# MIXER.net
KiCad netlist of a schematic drawn in Altium Designer
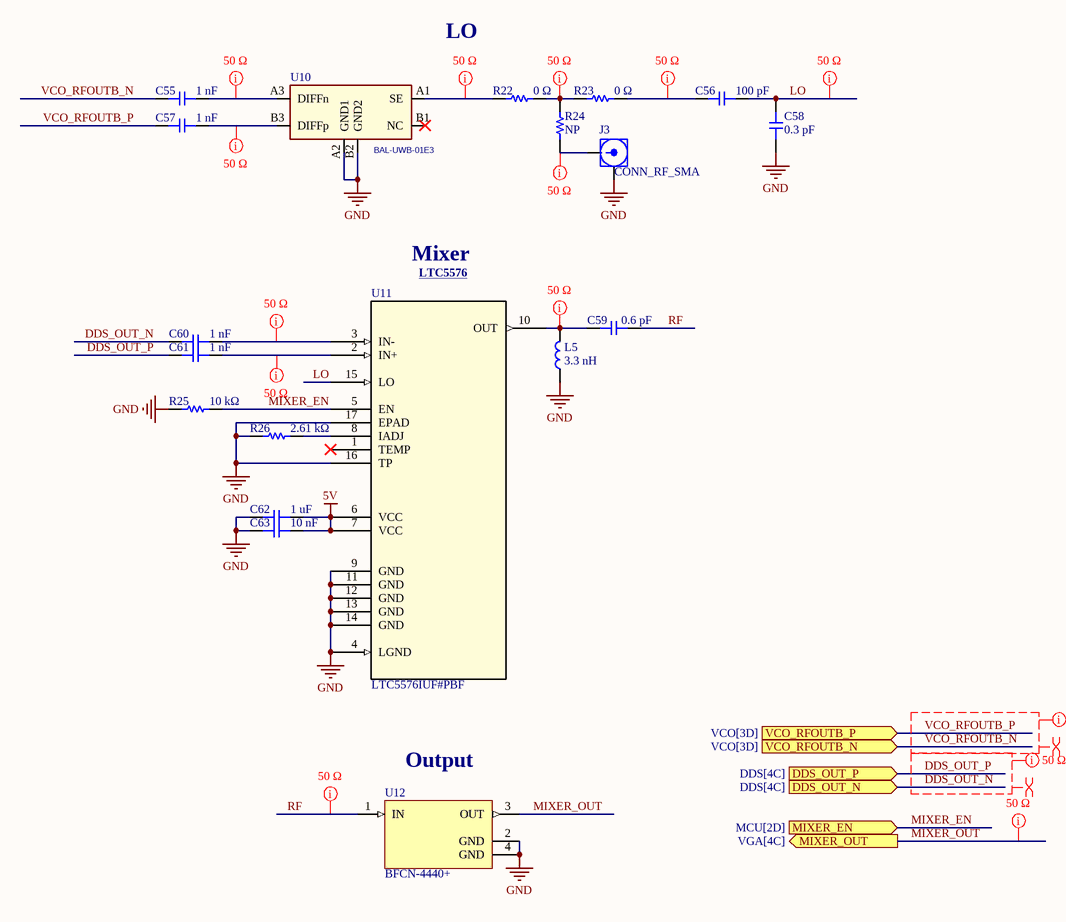
[diagram p0: MIXER.SchDoc]

(export (version "E")
  (design (tool "Eeschema 10.0.6"))
  (components
    (comp (ref "C55")
      (value "1 nF")
      (footprint "CAP_0402")
      (description "50V 1nF X7R ±10% 0402 Multilayer Ceramic Capacitors MLCC - SMD/SMT ROHS")
      (fields
        (field (name "MANUFACTURER") "Yageo")
        (field (name "MANUFACTURER PART NUMBER") "CC0402KRX7R9BB102")
      )
      (libsource (lib "Titan") (part "CAP"))
    )
    (comp (ref "C56")
      (value "100 pF")
      (footprint "CAP_0402")
      (description "50V 100pF NP0 ±5% 0402 Multilayer Ceramic Capacitors MLCC - SMD/SMT ROHS")
      (fields
        (field (name "MANUFACTURER") "Yageo")
        (field (name "MANUFACTURER PART NUMBER") "CC0402JRNPO9BN101")
      )
      (libsource (lib "Titan") (part "CAP"))
    )
    (comp (ref "C57")
      (value "1 nF")
      (footprint "CAP_0402")
      (description "50V 1nF X7R ±10% 0402 Multilayer Ceramic Capacitors MLCC - SMD/SMT ROHS")
      (fields
        (field (name "MANUFACTURER") "Yageo")
        (field (name "MANUFACTURER PART NUMBER") "CC0402KRX7R9BB102")
      )
      (libsource (lib "Titan") (part "CAP"))
    )
    (comp (ref "C58")
      (value "0.3 pF")
      (footprint "CAP_0402")
      (description "50V 0.3pF C0G 0402 Multilayer Ceramic Capacitors MLCC - SMD/SMT ROHS")
      (fields
        (field (name "MANUFACTURER") "Murata Electronics")
        (field (name "MANUFACTURER PART NUMBER") "GJM1555C1HR30WB01D")
      )
      (libsource (lib "Titan") (part "CAP"))
    )
    (comp (ref "C59")
      (value "0.6 pF")
      (footprint "CAP_0402")
      (description "50V 0.6pF C0G 0402 Multilayer Ceramic Capacitors MLCC - SMD/SMT ROHS")
      (fields
        (field (name "MANUFACTURER") "Murata Electronics")
        (field (name "MANUFACTURER PART NUMBER") "GJM1555C1HR60WB01D")
      )
      (libsource (lib "Titan") (part "CAP"))
    )
    (comp (ref "C60")
      (value "1 nF")
      (footprint "CAP_0402")
      (description "50V 1nF X7R ±10% 0402 Multilayer Ceramic Capacitors MLCC - SMD/SMT ROHS")
      (fields
        (field (name "MANUFACTURER") "Yageo")
        (field (name "MANUFACTURER PART NUMBER") "CC0402KRX7R9BB102")
      )
      (libsource (lib "Titan") (part "CAP"))
    )
    (comp (ref "C61")
      (value "1 nF")
      (footprint "CAP_0402")
      (description "50V 1nF X7R ±10% 0402 Multilayer Ceramic Capacitors MLCC - SMD/SMT ROHS")
      (fields
        (field (name "MANUFACTURER") "Yageo")
        (field (name "MANUFACTURER PART NUMBER") "CC0402KRX7R9BB102")
      )
      (libsource (lib "Titan") (part "CAP"))
    )
    (comp (ref "C62")
      (value "1 uF")
      (footprint "CAP_0603")
      (description "25V 1uF X7R ±10% 0603 Multilayer Ceramic Capacitors MLCC - SMD/SMT ROHS")
      (fields
        (field (name "MANUFACTURER") "Samsung Electro-Mechanics")
        (field (name "MANUFACTURER PART NUMBER") "CL10B105KA8NNNC")
      )
      (libsource (lib "Titan") (part "CAP"))
    )
    (comp (ref "C63")
      (value "10 nF")
      (footprint "CAP_0402")
      (description "50V 10nF X7R ±10% 0402 Multilayer Ceramic Capacitors MLCC - SMD/SMT ROHS")
      (fields
        (field (name "MANUFACTURER") "Yageo")
        (field (name "MANUFACTURER PART NUMBER") "CC0402KRX7R9BB103")
      )
      (libsource (lib "Titan") (part "CAP"))
    )
    (comp (ref "J3")
      (value "CONN_RF_SMA")
      (footprint "142-0701-801")
      (description "RF / Coaxial Connector, SMA Coaxial, Straight Jack, Solder, 50 ohm, Beryllium Copper")
      (fields
        (field (name "MANUFACTURER") "Cinch Connectivity Solutions Johnson")
        (field (name "MANUFACTURER PART NUMBER") "142-0701-801")
      )
      (libsource (lib "Titan") (part "CONN_RF_SMA"))
    )
    (comp (ref "L5")
      (value "3.3 nH")
      (footprint "IND_0402")
      (description "Ind RF Chip Unshielded Wirewound 3.3nH 0.1nH 100MHz 30Q-Factor Ferrite 2A 0402 Paper T/R")
      (fields
        (field (name "MANUFACTURER") "Murata Electronics")
        (field (name "MANUFACTURER PART NUMBER") "LQW15AN3N3B80D")
      )
      (libsource (lib "Titan") (part "IND"))
    )
    (comp (ref "R22")
      (value "0 Ω")
      (footprint "RES_0402")
      (description "GENERAL PURPOSE CHIP RESISTOR Metal Glaze/thick Film, 0.0625W, 0ohm, Surface Mount, 0402")
      (fields
        (field (name "MANUFACTURER") "Yageo")
        (field (name "MANUFACTURER PART NUMBER") "RC0402FR-070RL")
      )
      (libsource (lib "Titan") (part "RES"))
    )
    (comp (ref "R23")
      (value "0 Ω")
      (footprint "RES_0402")
      (description "GENERAL PURPOSE CHIP RESISTOR Metal Glaze/thick Film, 0.0625W, 0ohm, Surface Mount, 0402")
      (fields
        (field (name "MANUFACTURER") "Yageo")
        (field (name "MANUFACTURER PART NUMBER") "RC0402FR-070RL")
      )
      (libsource (lib "Titan") (part "RES"))
    )
    (comp (ref "R24")
      (value "NP")
      (footprint "RES_0402")
      (description "Resistor SMD Generic")
      (libsource (lib "Titan") (part "RES"))
    )
    (comp (ref "R25")
      (value "10 kΩ")
      (footprint "RES_0402")
      (description "Res Thick Film 0402 10K Ohm 1% 0.063W(1/16W) ±100ppm/C Pad SMD T/R")
      (fields
        (field (name "MANUFACTURER") "Yageo")
        (field (name "MANUFACTURER PART NUMBER") "RC0402FR-0710KL")
      )
      (libsource (lib "Titan") (part "RES"))
    )
    (comp (ref "R26")
      (value "2.61 kΩ")
      (footprint "RES_0402")
      (description "Fixed Resistor, Thin Film, 0.0625W, 2610ohm, 50V, 1% +/-Tol, 50ppm/Cel, Surface Mount, 0402")
      (fields
        (field (name "MANUFACTURER") "Yageo")
        (field (name "MANUFACTURER PART NUMBER") "RT0402FRE072K61L")
      )
      (libsource (lib "Titan") (part "RES"))
    )
    (comp (ref "U10")
      (value "BAL-UWB-01E3")
      (footprint "ST_CSP6_82x65P2x3_180x125x45")
      (description "Balun, 1dB, 8GHz, FLIP CHIP BUMPLESS CSPG, RoHS, Tape And Reel")
      (fields (field (name "MANUFACTURER") "STMicroelectronics"))
      (libsource (lib "BAL-UWB-01E3") (part "BAL-UWB-01E3"))
    )
    (comp (ref "U11")
      (value "LTC5576IUF#PBF")
      (footprint "QFN-16_UF_LIT")
      (description "IC Mixer Down Converter 16QFN \"rf Mixer IC Cellular, Wlan 3GHZ ~ 8GHZ 16-QFN (4X4)\"")
      (fields
        (field (name "MANUFACTURER") "Analog Devices")
        (field (name "COPYRIGHT") "Copyright (C) 2026 Ultra Librarian. All rights reserved.")
      )
      (libsource (lib "LTC5576IUFPBF") (part "LTC5576IUFPBF"))
    )
    (comp (ref "U12")
      (value "BFCN-4440+")
      (footprint "FV1206")
      (description "Ceramic BPF, 1 Section(s) Min, 1 Section(s) Max, 4440MHz")
      (fields (field (name "MANUFACTURER") "Mini-Circuits"))
      (libsource (lib "Titan") (part "BFCN-4440+"))
    )
  )
  (nets
    (net (code "1") (name "/DDS_OUT_N") (class "Default") (node (ref "C60") (pin "1") (pintype "passive")))
    (net (code "2") (name "/DDS_OUT_P") (class "Default") (node (ref "C61") (pin "1") (pintype "passive")))
    (net (code "3") (name "/LO") (class "Default")
      (node (ref "C56") (pin "2") (pintype "passive"))
      (node (ref "C58") (pin "2") (pintype "passive"))
      (node (ref "U11") (pin "15") (pinfunction "LO_15") (pintype "input"))
    )
    (net (code "4") (name "/MIXER_EN") (class "Default")
      (node (ref "R25") (pin "2") (pintype "passive"))
      (node (ref "U11") (pin "5") (pinfunction "EN_5") (pintype "passive"))
    )
    (net (code "5") (name "/MIXER_OUT") (class "Default")
      (node (ref "U12") (pin "3") (pinfunction "OUT_3") (pintype "output"))
    )
    (net (code "6") (name "/RF") (class "Default")
      (node (ref "C59") (pin "2") (pintype "passive"))
      (node (ref "U12") (pin "1") (pinfunction "IN_1") (pintype "input"))
    )
    (net (code "7") (name "/VCO_RFOUTB_N") (class "Default") (node (ref "C55") (pin "2") (pintype "passive")))
    (net (code "8") (name "/VCO_RFOUTB_P") (class "Default") (node (ref "C57") (pin "2") (pintype "passive")))
    (net (code "9") (name "5V") (class "Default")
      (node (ref "C62") (pin "2") (pintype "passive"))
      (node (ref "C63") (pin "2") (pintype "passive"))
      (node (ref "U11") (pin "6") (pinfunction "VCC_6") (pintype "power_in"))
      (node (ref "U11") (pin "7") (pinfunction "VCC_7") (pintype "power_in"))
    )
    (net (code "10") (name "GND") (class "Default")
      (node (ref "C58") (pin "1") (pintype "passive"))
      (node (ref "C62") (pin "1") (pintype "passive"))
      (node (ref "C63") (pin "1") (pintype "passive"))
      (node (ref "J3") (pin "2") (pintype "passive"))
      (node (ref "L5") (pin "1") (pintype "passive"))
      (node (ref "R25") (pin "1") (pintype "passive"))
      (node (ref "R26") (pin "1") (pintype "passive"))
      (node (ref "U10") (pin "A2") (pinfunction "GND1_A2") (pintype "passive"))
      (node (ref "U10") (pin "B2") (pinfunction "GND2_B2") (pintype "passive"))
      (node (ref "U11") (pin "11") (pinfunction "GND_11") (pintype "power_in"))
      (node (ref "U11") (pin "12") (pinfunction "GND_12") (pintype "power_in"))
      (node (ref "U11") (pin "13") (pinfunction "GND_13") (pintype "power_in"))
      (node (ref "U11") (pin "14") (pinfunction "GND_14") (pintype "power_in"))
      (node (ref "U11") (pin "16") (pinfunction "TP_16") (pintype "passive"))
      (node (ref "U11") (pin "17") (pinfunction "EPAD_17") (pintype "passive"))
      (node (ref "U11") (pin "4") (pinfunction "LGND_4") (pintype "input"))
      (node (ref "U11") (pin "9") (pinfunction "GND_9") (pintype "power_in"))
      (node (ref "U12") (pin "2") (pinfunction "GND_2") (pintype "power_in"))
      (node (ref "U12") (pin "4") (pinfunction "GND_4") (pintype "power_in"))
    )
    (net (code "11") (name "Net-(C56-Pad1)") (class "Default")
      (node (ref "C56") (pin "1") (pintype "passive"))
      (node (ref "R23") (pin "2") (pintype "passive"))
    )
    (net (code "12") (name "Net-(J3-Pad1)") (class "Default")
      (node (ref "J3") (pin "1") (pintype "passive"))
      (node (ref "R24") (pin "1") (pintype "passive"))
    )
    (net (code "13") (name "Net-(R22-Pad2)") (class "Default")
      (node (ref "R22") (pin "2") (pintype "passive"))
      (node (ref "R23") (pin "1") (pintype "passive"))
      (node (ref "R24") (pin "2") (pintype "passive"))
    )
    (net (code "14") (name "Net-(U10-DIFFn)") (class "Default")
      (node (ref "C55") (pin "1") (pintype "passive"))
      (node (ref "U10") (pin "A3") (pinfunction "DIFFn_A3") (pintype "passive"))
    )
    (net (code "15") (name "Net-(U10-DIFFp)") (class "Default")
      (node (ref "C57") (pin "1") (pintype "passive"))
      (node (ref "U10") (pin "B3") (pinfunction "DIFFp_B3") (pintype "passive"))
    )
    (net (code "16") (name "Net-(U10-SE)") (class "Default")
      (node (ref "R22") (pin "1") (pintype "passive"))
      (node (ref "U10") (pin "A1") (pinfunction "SE_A1") (pintype "passive"))
    )
    (net (code "17") (name "Net-(U11-IADJ)") (class "Default")
      (node (ref "R26") (pin "2") (pintype "passive"))
      (node (ref "U11") (pin "8") (pinfunction "IADJ_8") (pintype "passive"))
    )
    (net (code "18") (name "Net-(U11-IN+)") (class "Default")
      (node (ref "C61") (pin "2") (pintype "passive"))
      (node (ref "U11") (pin "2") (pinfunction "IN+_2") (pintype "input"))
    )
    (net (code "19") (name "Net-(U11-IN-)") (class "Default")
      (node (ref "C60") (pin "2") (pintype "passive"))
      (node (ref "U11") (pin "3") (pinfunction "IN-_3") (pintype "input"))
    )
    (net (code "20") (name "Net-(U11-OUT)") (class "Default")
      (node (ref "C59") (pin "1") (pintype "passive"))
      (node (ref "L5") (pin "2") (pintype "passive"))
      (node (ref "U11") (pin "10") (pinfunction "OUT_10") (pintype "output"))
    )
    (net (code "21") (name "unconnected-(U10-NC-PadB1)") (class "Default")
      (node (ref "U10") (pin "B1") (pinfunction "NC_B1") (pintype "passive+no_connect"))
    )
    (net (code "22") (name "unconnected-(U11-TEMP-Pad1)") (class "Default")
      (node (ref "U11") (pin "1") (pinfunction "TEMP_1") (pintype "passive+no_connect"))
    )
  )
)
